# Carduino.net
KiCad netlist of a schematic drawn in EAGLE
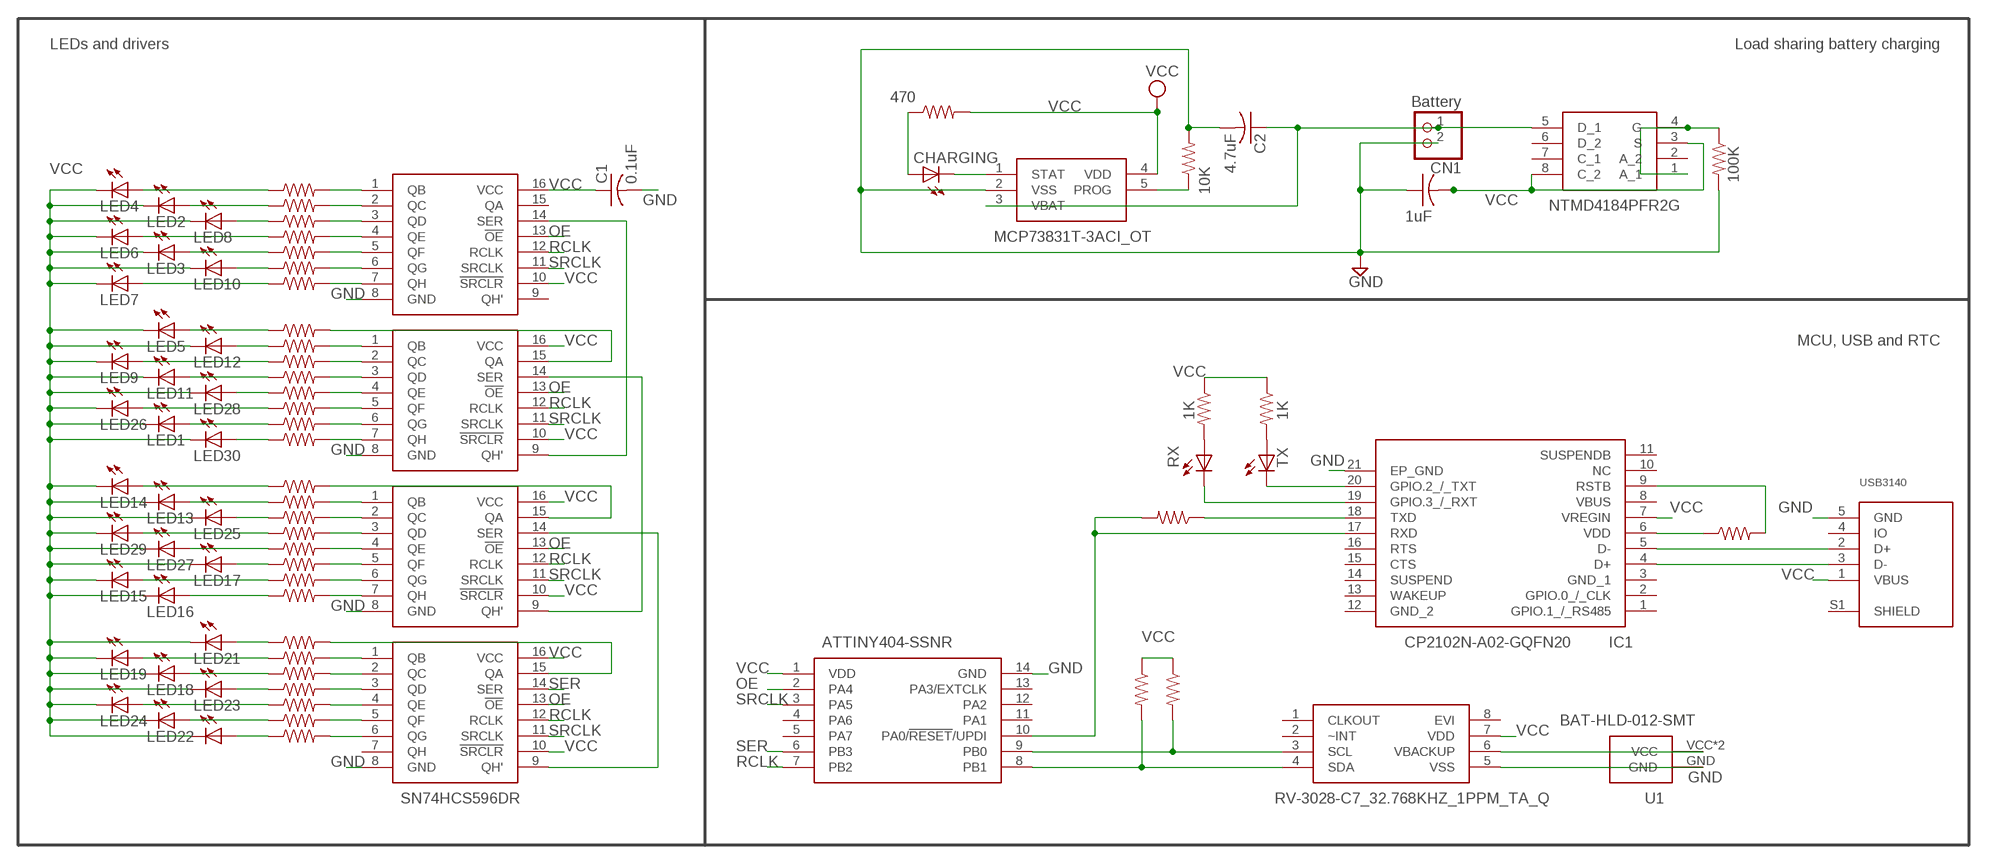
[diagram p0: schematic, sheet 1]

(export (version "E")
  (design (tool "Eeschema 10.0.6"))
  (components
    (comp (ref "C1")
      (value "0.1uF")
      (footprint "eagle-import:C1206")
      (libsource (lib "eagle-import") (part "C-USC1206"))
    )
    (comp (ref "C2")
      (value "4.7uF")
      (footprint "eagle-import:C1206")
      (libsource (lib "eagle-import") (part "C-USC1206"))
    )
    (comp (ref "C3")
      (value "1uF")
      (footprint "eagle-import:C1206")
      (libsource (lib "eagle-import") (part "C-USC1206"))
    )
    (comp (ref "CHARGING")
      (value "Red")
      (footprint "eagle-import:CHIP-LED0805")
      (libsource (lib "eagle-import") (part "LEDCHIP-LED0805"))
    )
    (comp (ref "CN1")
      (value "Battery")
      (footprint "eagle-import:JST-PH-2-SMT-RA")
      (libsource (lib "eagle-import") (part "JST_2PIN-SMT-RA"))
    )
    (comp (ref "IC1")
      (value "CP2102N-A02-GQFN20")
      (footprint "eagle-import:CP2102NA02GQFN20")
      (fields (field (name "MOUSER_PART_NUMBER") "634-CP2102NA02GQFN20"))
      (libsource (lib "eagle-import") (part "CP2102N-A02-GQFN20"))
    )
    (comp (ref "IC3")
      (value "SN74HCS596DR")
      (footprint "eagle-import:SOIC127P600X175-16N")
      (fields (field (name "MOUSER_PART_NUMBER") "595-SN74HCS596DR"))
      (libsource (lib "eagle-import") (part "SN74HCS596DR"))
    )
    (comp (ref "IC4")
      (value "SN74HCS596DR")
      (footprint "eagle-import:SOIC127P600X175-16N")
      (fields (field (name "MOUSER_PART_NUMBER") "595-SN74HCS596DR"))
      (libsource (lib "eagle-import") (part "SN74HCS596DR"))
    )
    (comp (ref "IC5")
      (value "SN74HCS596DR")
      (footprint "eagle-import:SOIC127P600X175-16N")
      (fields (field (name "MOUSER_PART_NUMBER") "595-SN74HCS596DR"))
      (libsource (lib "eagle-import") (part "SN74HCS596DR"))
    )
    (comp (ref "IC6")
      (value "SN74HCS596DR")
      (footprint "eagle-import:SOIC127P600X175-16N")
      (fields (field (name "MOUSER_PART_NUMBER") "595-SN74HCS596DR"))
      (libsource (lib "eagle-import") (part "SN74HCS596DR"))
    )
    (comp (ref "IC7")
      (value "NTMD4184PFR2G")
      (footprint "eagle-import:SOIC127P600X175-8N")
      (fields (field (name "MOUSER_PART_NUMBER") "863-NTMD4184PFR2G"))
      (libsource (lib "eagle-import") (part "NTMD4184PFR2G"))
    )
    (comp (ref "IC8")
      (value "ATTINY404-SSNR")
      (footprint "eagle-import:SOIC127P600X175-14N")
      (fields (field (name "MOUSER_PART_NUMBER") "556-ATTINY404-SSNR"))
      (libsource (lib "eagle-import") (part "ATTINY404-SSNR"))
    )
    (comp (ref "IC9")
      (value "MCP73831T-3ACI_OT")
      (footprint "eagle-import:SOT95P270X145-5N")
      (fields
        (field (name "MANUFACTURER_PART_NUMBER") "MCP73831T-3ACI/OT")
        (field (name "MOUSER_PART_NUMBER") "579-MCP73831T-3ACIOT")
      )
      (libsource (lib "eagle-import") (part "MCP73831T-3ACI_OT"))
    )
    (comp (ref "IC11")
      (value "RV-3028-C7_32.768KHZ_1PPM_TA_Q")
      (footprint "eagle-import:RV3028C732768KHZ1PPMTAQC")
      (fields
        (field (name "MANUFACTURER_PART_NUMBER") "RV-3028-C7 32.768kHz 1ppm TA QC")
        (field (name "MOUSER_PART_NUMBER") "428-203591-MG01")
      )
      (libsource (lib "eagle-import") (part "RV-3028-C7_32.768KHZ_1PPM_TA_Q"))
    )
    (comp (ref "LED1")
      (value "LUXEON2835L128-1890NA3500001")
      (footprint "eagle-import:LUXEON2835")
      (libsource (lib "eagle-import") (part "LUXEON2835L128-1890NA3500001"))
    )
    (comp (ref "LED2")
      (value "LUXEON2835L128-1890NA3500001")
      (footprint "eagle-import:LUXEON2835")
      (libsource (lib "eagle-import") (part "LUXEON2835L128-1890NA3500001"))
    )
    (comp (ref "LED3")
      (value "LUXEON2835L128-1890NA3500001")
      (footprint "eagle-import:LUXEON2835")
      (libsource (lib "eagle-import") (part "LUXEON2835L128-1890NA3500001"))
    )
    (comp (ref "LED4")
      (value "LUXEON2835L128-1890NA3500001")
      (footprint "eagle-import:LUXEON2835")
      (libsource (lib "eagle-import") (part "LUXEON2835L128-1890NA3500001"))
    )
    (comp (ref "LED5")
      (value "LUXEON2835L128-1890NA3500001")
      (footprint "eagle-import:LUXEON2835")
      (libsource (lib "eagle-import") (part "LUXEON2835L128-1890NA3500001"))
    )
    (comp (ref "LED6")
      (value "LUXEON2835L128-1890NA3500001")
      (footprint "eagle-import:LUXEON2835")
      (libsource (lib "eagle-import") (part "LUXEON2835L128-1890NA3500001"))
    )
    (comp (ref "LED7")
      (value "LUXEON2835L128-1890NA3500001")
      (footprint "eagle-import:LUXEON2835")
      (libsource (lib "eagle-import") (part "LUXEON2835L128-1890NA3500001"))
    )
    (comp (ref "LED8")
      (value "LUXEON2835L128-1890NA3500001")
      (footprint "eagle-import:LUXEON2835")
      (libsource (lib "eagle-import") (part "LUXEON2835L128-1890NA3500001"))
    )
    (comp (ref "LED9")
      (value "LUXEON2835L128-1890NA3500001")
      (footprint "eagle-import:LUXEON2835")
      (libsource (lib "eagle-import") (part "LUXEON2835L128-1890NA3500001"))
    )
    (comp (ref "LED10")
      (value "LUXEON2835L128-1890NA3500001")
      (footprint "eagle-import:LUXEON2835")
      (libsource (lib "eagle-import") (part "LUXEON2835L128-1890NA3500001"))
    )
    (comp (ref "LED11")
      (value "LUXEON2835L128-1890NA3500001")
      (footprint "eagle-import:LUXEON2835")
      (libsource (lib "eagle-import") (part "LUXEON2835L128-1890NA3500001"))
    )
    (comp (ref "LED12")
      (value "LUXEON2835L128-1890NA3500001")
      (footprint "eagle-import:LUXEON2835")
      (libsource (lib "eagle-import") (part "LUXEON2835L128-1890NA3500001"))
    )
    (comp (ref "LED13")
      (value "LUXEON2835L128-1890NA3500001")
      (footprint "eagle-import:LUXEON2835")
      (libsource (lib "eagle-import") (part "LUXEON2835L128-1890NA3500001"))
    )
    (comp (ref "LED14")
      (value "LUXEON2835L128-1890NA3500001")
      (footprint "eagle-import:LUXEON2835")
      (libsource (lib "eagle-import") (part "LUXEON2835L128-1890NA3500001"))
    )
    (comp (ref "LED15")
      (value "LUXEON2835L128-1890NA3500001")
      (footprint "eagle-import:LUXEON2835")
      (libsource (lib "eagle-import") (part "LUXEON2835L128-1890NA3500001"))
    )
    (comp (ref "LED16")
      (value "LUXEON2835L128-1890NA3500001")
      (footprint "eagle-import:LUXEON2835")
      (libsource (lib "eagle-import") (part "LUXEON2835L128-1890NA3500001"))
    )
    (comp (ref "LED17")
      (value "LUXEON2835L128-1890NA3500001")
      (footprint "eagle-import:LUXEON2835")
      (libsource (lib "eagle-import") (part "LUXEON2835L128-1890NA3500001"))
    )
    (comp (ref "LED18")
      (value "LUXEON2835L128-1890NA3500001")
      (footprint "eagle-import:LUXEON2835")
      (libsource (lib "eagle-import") (part "LUXEON2835L128-1890NA3500001"))
    )
    (comp (ref "LED19")
      (value "LUXEON2835L128-1890NA3500001")
      (footprint "eagle-import:LUXEON2835")
      (libsource (lib "eagle-import") (part "LUXEON2835L128-1890NA3500001"))
    )
    (comp (ref "LED20")
      (value "LUXEON2835L128-1890NA3500001")
      (footprint "eagle-import:LUXEON2835")
      (libsource (lib "eagle-import") (part "LUXEON2835L128-1890NA3500001"))
    )
    (comp (ref "LED21")
      (value "LUXEON2835L128-1890NA3500001")
      (footprint "eagle-import:LUXEON2835")
      (libsource (lib "eagle-import") (part "LUXEON2835L128-1890NA3500001"))
    )
    (comp (ref "LED22")
      (value "LUXEON2835L128-1890NA3500001")
      (footprint "eagle-import:LUXEON2835")
      (libsource (lib "eagle-import") (part "LUXEON2835L128-1890NA3500001"))
    )
    (comp (ref "LED23")
      (value "LUXEON2835L128-1890NA3500001")
      (footprint "eagle-import:LUXEON2835")
      (libsource (lib "eagle-import") (part "LUXEON2835L128-1890NA3500001"))
    )
    (comp (ref "LED24")
      (value "LUXEON2835L128-1890NA3500001")
      (footprint "eagle-import:LUXEON2835")
      (libsource (lib "eagle-import") (part "LUXEON2835L128-1890NA3500001"))
    )
    (comp (ref "LED25")
      (value "LUXEON2835L128-1890NA3500001")
      (footprint "eagle-import:LUXEON2835")
      (libsource (lib "eagle-import") (part "LUXEON2835L128-1890NA3500001"))
    )
    (comp (ref "LED26")
      (value "LUXEON2835L128-1890NA3500001")
      (footprint "eagle-import:LUXEON2835")
      (libsource (lib "eagle-import") (part "LUXEON2835L128-1890NA3500001"))
    )
    (comp (ref "LED27")
      (value "LUXEON2835L128-1890NA3500001")
      (footprint "eagle-import:LUXEON2835")
      (libsource (lib "eagle-import") (part "LUXEON2835L128-1890NA3500001"))
    )
    (comp (ref "LED28")
      (value "LUXEON2835L128-1890NA3500001")
      (footprint "eagle-import:LUXEON2835")
      (libsource (lib "eagle-import") (part "LUXEON2835L128-1890NA3500001"))
    )
    (comp (ref "LED29")
      (value "LUXEON2835L128-1890NA3500001")
      (footprint "eagle-import:LUXEON2835")
      (libsource (lib "eagle-import") (part "LUXEON2835L128-1890NA3500001"))
    )
    (comp (ref "LED30")
      (value "LUXEON2835L128-1890NA3500001")
      (footprint "eagle-import:LUXEON2835")
      (libsource (lib "eagle-import") (part "LUXEON2835L128-1890NA3500001"))
    )
    (comp (ref "R1")
      (value "470")
      (footprint "eagle-import:R0805")
      (libsource (lib "eagle-import") (part "R-US_R0805"))
    )
    (comp (ref "R2")
      (value "1K")
      (footprint "eagle-import:R0805")
      (libsource (lib "eagle-import") (part "R-US_R0805"))
    )
    (comp (ref "R3")
      (value "1K")
      (footprint "eagle-import:R0805")
      (libsource (lib "eagle-import") (part "R-US_R0805"))
    )
    (comp (ref "R4")
      (value "4.7K")
      (footprint "eagle-import:R0805")
      (libsource (lib "eagle-import") (part "R-US_R0805"))
    )
    (comp (ref "R5")
      (value "4.7K")
      (footprint "eagle-import:R0805")
      (libsource (lib "eagle-import") (part "R-US_R0805"))
    )
    (comp (ref "R7")
      (value "1K")
      (footprint "eagle-import:R0805")
      (libsource (lib "eagle-import") (part "R-US_R0805"))
    )
    (comp (ref "R8")
      (value "1K")
      (footprint "eagle-import:R0805")
      (libsource (lib "eagle-import") (part "R-US_R0805"))
    )
    (comp (ref "R9")
      (value "1K")
      (footprint "eagle-import:R0805")
      (libsource (lib "eagle-import") (part "R-US_R0805"))
    )
    (comp (ref "R10")
      (value "1K")
      (footprint "eagle-import:R0805")
      (libsource (lib "eagle-import") (part "R-US_R0805"))
    )
    (comp (ref "R11")
      (value "1K")
      (footprint "eagle-import:R0805")
      (libsource (lib "eagle-import") (part "R-US_R0805"))
    )
    (comp (ref "R12")
      (value "1K")
      (footprint "eagle-import:R0805")
      (libsource (lib "eagle-import") (part "R-US_R0805"))
    )
    (comp (ref "R13")
      (value "1K")
      (footprint "eagle-import:R0805")
      (libsource (lib "eagle-import") (part "R-US_R0805"))
    )
    (comp (ref "R14")
      (value "1K")
      (footprint "eagle-import:R0805")
      (libsource (lib "eagle-import") (part "R-US_R0805"))
    )
    (comp (ref "R15")
      (value "1K")
      (footprint "eagle-import:R0805")
      (libsource (lib "eagle-import") (part "R-US_R0805"))
    )
    (comp (ref "R16")
      (value "470")
      (footprint "eagle-import:R0805")
      (libsource (lib "eagle-import") (part "R-US_R0805"))
    )
    (comp (ref "R17")
      (value "1K")
      (footprint "eagle-import:R0805")
      (libsource (lib "eagle-import") (part "R-US_R0805"))
    )
    (comp (ref "R18")
      (value "1K")
      (footprint "eagle-import:R0805")
      (libsource (lib "eagle-import") (part "R-US_R0805"))
    )
    (comp (ref "R19")
      (value "1K")
      (footprint "eagle-import:R0805")
      (libsource (lib "eagle-import") (part "R-US_R0805"))
    )
    (comp (ref "R20")
      (value "1K")
      (footprint "eagle-import:R0805")
      (libsource (lib "eagle-import") (part "R-US_R0805"))
    )
    (comp (ref "R21")
      (value "100K")
      (footprint "eagle-import:R0805")
      (libsource (lib "eagle-import") (part "R-US_R0805"))
    )
    (comp (ref "R22")
      (value "10K")
      (footprint "eagle-import:R0805")
      (libsource (lib "eagle-import") (part "R-US_R0805"))
    )
    (comp (ref "R23")
      (value "1K")
      (footprint "eagle-import:R0805")
      (libsource (lib "eagle-import") (part "R-US_R0805"))
    )
    (comp (ref "R31")
      (value "1K")
      (footprint "eagle-import:R0805")
      (libsource (lib "eagle-import") (part "R-US_R0805"))
    )
    (comp (ref "R32")
      (value "1K")
      (footprint "eagle-import:R0805")
      (libsource (lib "eagle-import") (part "R-US_R0805"))
    )
    (comp (ref "R33")
      (value "1K")
      (footprint "eagle-import:R0805")
      (libsource (lib "eagle-import") (part "R-US_R0805"))
    )
    (comp (ref "R34")
      (value "1K")
      (footprint "eagle-import:R0805")
      (libsource (lib "eagle-import") (part "R-US_R0805"))
    )
    (comp (ref "R35")
      (value "1K")
      (footprint "eagle-import:R0805")
      (libsource (lib "eagle-import") (part "R-US_R0805"))
    )
    (comp (ref "R36")
      (value "1K")
      (footprint "eagle-import:R0805")
      (libsource (lib "eagle-import") (part "R-US_R0805"))
    )
    (comp (ref "R37")
      (value "1K")
      (footprint "eagle-import:R0805")
      (libsource (lib "eagle-import") (part "R-US_R0805"))
    )
    (comp (ref "R38")
      (value "1K")
      (footprint "eagle-import:R0805")
      (libsource (lib "eagle-import") (part "R-US_R0805"))
    )
    (comp (ref "R39")
      (value "1K")
      (footprint "eagle-import:R0805")
      (libsource (lib "eagle-import") (part "R-US_R0805"))
    )
    (comp (ref "R40")
      (value "1K")
      (footprint "eagle-import:R0805")
      (libsource (lib "eagle-import") (part "R-US_R0805"))
    )
    (comp (ref "R41")
      (value "1K")
      (footprint "eagle-import:R0805")
      (libsource (lib "eagle-import") (part "R-US_R0805"))
    )
    (comp (ref "R42")
      (value "1K")
      (footprint "eagle-import:R0805")
      (libsource (lib "eagle-import") (part "R-US_R0805"))
    )
    (comp (ref "R43")
      (value "1K")
      (footprint "eagle-import:R0805")
      (libsource (lib "eagle-import") (part "R-US_R0805"))
    )
    (comp (ref "R44")
      (value "1K")
      (footprint "eagle-import:R0805")
      (libsource (lib "eagle-import") (part "R-US_R0805"))
    )
    (comp (ref "R45")
      (value "1K")
      (footprint "eagle-import:R0805")
      (libsource (lib "eagle-import") (part "R-US_R0805"))
    )
    (comp (ref "R46")
      (value "1K")
      (footprint "eagle-import:R0805")
      (libsource (lib "eagle-import") (part "R-US_R0805"))
    )
    (comp (ref "R47")
      (value "1K")
      (footprint "eagle-import:R0805")
      (libsource (lib "eagle-import") (part "R-US_R0805"))
    )
    (comp (ref "RX")
      (value "Green")
      (footprint "eagle-import:CHIP-LED0805")
      (libsource (lib "eagle-import") (part "LEDCHIP-LED0805"))
    )
    (comp (ref "TX")
      (value "Red")
      (footprint "eagle-import:CHIP-LED0805")
      (libsource (lib "eagle-import") (part "LEDCHIP-LED0805"))
    )
    (comp (ref "U$5")
      (value "USB3140")
      (footprint "eagle-import:USB3140-30-0170-0-C")
      (libsource (lib "eagle-import") (part "USB3140"))
    )
    (comp (ref "U1")
      (value "BAT-HLD-012-SMT")
      (footprint "eagle-import:BATHLD012SMT")
      (fields (field (name "MOUSER_PART_NUMBER") "712-BAT-HLD-012-SMT"))
      (libsource (lib "eagle-import") (part "BAT-HLD-012-SMT"))
    )
  )
  (nets
    (net (code "1") (name "/OE") (class "Default")
      (node (ref "IC3") (pin "13") (pinfunction "~{OE}_13") (pintype "bidirectional"))
      (node (ref "IC4") (pin "13") (pinfunction "~{OE}_13") (pintype "bidirectional"))
      (node (ref "IC5") (pin "13") (pinfunction "~{OE}_13") (pintype "bidirectional"))
      (node (ref "IC6") (pin "13") (pinfunction "~{OE}_13") (pintype "bidirectional"))
      (node (ref "IC8") (pin "2") (pinfunction "PA4_2") (pintype "bidirectional"))
    )
    (net (code "2") (name "/RCLK") (class "Default")
      (node (ref "IC3") (pin "12") (pinfunction "RCLK_12") (pintype "bidirectional"))
      (node (ref "IC4") (pin "12") (pinfunction "RCLK_12") (pintype "bidirectional"))
      (node (ref "IC5") (pin "12") (pinfunction "RCLK_12") (pintype "bidirectional"))
      (node (ref "IC6") (pin "12") (pinfunction "RCLK_12") (pintype "bidirectional"))
      (node (ref "IC8") (pin "7") (pinfunction "PB2_7") (pintype "bidirectional"))
    )
    (net (code "3") (name "/SER") (class "Default")
      (node (ref "IC6") (pin "14") (pinfunction "SER_14") (pintype "bidirectional"))
      (node (ref "IC8") (pin "6") (pinfunction "PB3_6") (pintype "bidirectional"))
    )
    (net (code "4") (name "/SRCLK") (class "Default")
      (node (ref "IC3") (pin "11") (pinfunction "SRCLK_11") (pintype "bidirectional"))
      (node (ref "IC4") (pin "11") (pinfunction "SRCLK_11") (pintype "bidirectional"))
      (node (ref "IC5") (pin "11") (pinfunction "SRCLK_11") (pintype "bidirectional"))
      (node (ref "IC6") (pin "11") (pinfunction "SRCLK_11") (pintype "bidirectional"))
      (node (ref "IC8") (pin "3") (pinfunction "PA5_3") (pintype "bidirectional"))
    )
    (net (code "5") (name "GND") (class "Default")
      (node (ref "C1") (pin "2") (pinfunction "2_2") (pintype "passive"))
      (node (ref "C2") (pin "2") (pinfunction "2_2") (pintype "passive"))
      (node (ref "C3") (pin "1") (pinfunction "1_1") (pintype "passive"))
      (node (ref "CN1") (pin "2") (pinfunction "1_2") (pintype "passive"))
      (node (ref "IC1") (pin "21") (pinfunction "EP_GND_21") (pintype "bidirectional"))
      (node (ref "IC11") (pin "5") (pinfunction "VSS_5") (pintype "bidirectional"))
      (node (ref "IC3") (pin "8") (pinfunction "GND_8") (pintype "bidirectional"))
      (node (ref "IC4") (pin "8") (pinfunction "GND_8") (pintype "bidirectional"))
      (node (ref "IC5") (pin "8") (pinfunction "GND_8") (pintype "bidirectional"))
      (node (ref "IC6") (pin "8") (pinfunction "GND_8") (pintype "bidirectional"))
      (node (ref "IC8") (pin "14") (pinfunction "GND_14") (pintype "bidirectional"))
      (node (ref "IC9") (pin "2") (pinfunction "VSS_2") (pintype "bidirectional"))
      (node (ref "R21") (pin "2") (pinfunction "2_2") (pintype "passive"))
      (node (ref "R22") (pin "2") (pinfunction "2_2") (pintype "passive"))
      (node (ref "U$5") (pin "5") (pinfunction "GND_5") (pintype "passive"))
      (node (ref "U1") (pin "GND") (pinfunction "GND_GND") (pintype "bidirectional"))
    )
    (net (code "6") (name "Net-(CHARGING-PadA)") (class "Default")
      (node (ref "CHARGING") (pin "A") (pinfunction "A_A") (pintype "passive"))
      (node (ref "R16") (pin "1") (pinfunction "1_1") (pintype "passive"))
    )
    (net (code "7") (name "Net-(CN1-2)") (class "Default")
      (node (ref "C2") (pin "1") (pinfunction "1_1") (pintype "passive"))
      (node (ref "CN1") (pin "1") (pinfunction "2_1") (pintype "passive"))
      (node (ref "IC7") (pin "5") (pinfunction "D_1_5") (pintype "bidirectional"))
      (node (ref "IC9") (pin "3") (pinfunction "VBAT_3") (pintype "bidirectional"))
    )
    (net (code "8") (name "Net-(IC1-D+)") (class "Default")
      (node (ref "IC1") (pin "4") (pinfunction "D+_4") (pintype "bidirectional"))
      (node (ref "U$5") (pin "3") (pinfunction "D-_3") (pintype "passive"))
    )
    (net (code "9") (name "Net-(IC1-D-)") (class "Default")
      (node (ref "IC1") (pin "5") (pinfunction "D-_5") (pintype "bidirectional"))
      (node (ref "U$5") (pin "2") (pinfunction "D+_2") (pintype "passive"))
    )
    (net (code "10") (name "Net-(IC1-GPIO.2_{slash}_TXT)") (class "Default")
      (node (ref "IC1") (pin "20") (pinfunction "GPIO.2_/_TXT_20") (pintype "bidirectional"))
      (node (ref "TX") (pin "C") (pinfunction "C_C") (pintype "passive"))
    )
    (net (code "11") (name "Net-(IC1-GPIO.3_{slash}_RXT)") (class "Default")
      (node (ref "IC1") (pin "19") (pinfunction "GPIO.3_/_RXT_19") (pintype "bidirectional"))
      (node (ref "RX") (pin "C") (pinfunction "C_C") (pintype "passive"))
    )
    (net (code "12") (name "Net-(IC1-RSTB)") (class "Default")
      (node (ref "IC1") (pin "9") (pinfunction "RSTB_9") (pintype "bidirectional"))
      (node (ref "R23") (pin "2") (pinfunction "2_2") (pintype "passive"))
    )
    (net (code "13") (name "Net-(IC1-RXD)") (class "Default")
      (node (ref "IC1") (pin "17") (pinfunction "RXD_17") (pintype "bidirectional"))
      (node (ref "IC8") (pin "10") (pinfunction "PA0/~{RESET}/UPDI_10") (pintype "bidirectional"))
      (node (ref "R1") (pin "2") (pinfunction "2_2") (pintype "passive"))
    )
    (net (code "14") (name "Net-(IC1-TXD)") (class "Default")
      (node (ref "IC1") (pin "18") (pinfunction "TXD_18") (pintype "bidirectional"))
      (node (ref "R1") (pin "1") (pinfunction "1_1") (pintype "passive"))
    )
    (net (code "15") (name "Net-(IC1-VDD)") (class "Default")
      (node (ref "IC1") (pin "6") (pinfunction "VDD_6") (pintype "bidirectional"))
      (node (ref "R23") (pin "1") (pinfunction "1_1") (pintype "passive"))
    )
    (net (code "16") (name "Net-(IC3-QB)") (class "Default")
      (node (ref "IC3") (pin "1") (pinfunction "QB_1") (pintype "bidirectional"))
      (node (ref "R15") (pin "2") (pinfunction "2_2") (pintype "passive"))
    )
    (net (code "17") (name "Net-(IC3-QC)") (class "Default")
      (node (ref "IC3") (pin "2") (pinfunction "QC_2") (pintype "bidirectional"))
      (node (ref "R14") (pin "2") (pinfunction "2_2") (pintype "passive"))
    )
    (net (code "18") (name "Net-(IC3-QD)") (class "Default")
      (node (ref "IC3") (pin "3") (pinfunction "QD_3") (pintype "bidirectional"))
      (node (ref "R13") (pin "2") (pinfunction "2_2") (pintype "passive"))
    )
    (net (code "19") (name "Net-(IC3-QE)") (class "Default")
      (node (ref "IC3") (pin "4") (pinfunction "QE_4") (pintype "bidirectional"))
      (node (ref "R12") (pin "2") (pinfunction "2_2") (pintype "passive"))
    )
    (net (code "20") (name "Net-(IC3-QF)") (class "Default")
      (node (ref "IC3") (pin "5") (pinfunction "QF_5") (pintype "bidirectional"))
      (node (ref "R11") (pin "2") (pinfunction "2_2") (pintype "passive"))
    )
    (net (code "21") (name "Net-(IC3-QG)") (class "Default")
      (node (ref "IC3") (pin "6") (pinfunction "QG_6") (pintype "bidirectional"))
      (node (ref "R10") (pin "2") (pinfunction "2_2") (pintype "passive"))
    )
    (net (code "22") (name "Net-(IC3-QH)") (class "Default")
      (node (ref "IC3") (pin "7") (pinfunction "QH_7") (pintype "bidirectional"))
      (node (ref "R9") (pin "2") (pinfunction "2_2") (pintype "passive"))
    )
    (net (code "23") (name "Net-(IC3-SER)") (class "Default")
      (node (ref "IC3") (pin "14") (pinfunction "SER_14") (pintype "bidirectional"))
      (node (ref "IC4") (pin "9") (pinfunction "QH'_9") (pintype "bidirectional"))
    )
    (net (code "24") (name "Net-(IC4-QA)") (class "Default")
      (node (ref "IC4") (pin "15") (pinfunction "QA_15") (pintype "bidirectional"))
      (node (ref "R8") (pin "2") (pinfunction "2_2") (pintype "passive"))
    )
    (net (code "25") (name "Net-(IC4-QB)") (class "Default")
      (node (ref "IC4") (pin "1") (pinfunction "QB_1") (pintype "bidirectional"))
      (node (ref "R7") (pin "2") (pinfunction "2_2") (pintype "passive"))
    )
    (net (code "26") (name "Net-(IC4-QC)") (class "Default")
      (node (ref "IC4") (pin "2") (pinfunction "QC_2") (pintype "bidirectional"))
      (node (ref "R17") (pin "2") (pinfunction "2_2") (pintype "passive"))
    )
    (net (code "27") (name "Net-(IC4-QD)") (class "Default")
      (node (ref "IC4") (pin "3") (pinfunction "QD_3") (pintype "bidirectional"))
      (node (ref "R18") (pin "2") (pinfunction "2_2") (pintype "passive"))
    )
    (net (code "28") (name "Net-(IC4-QE)") (class "Default")
      (node (ref "IC4") (pin "4") (pinfunction "QE_4") (pintype "bidirectional"))
      (node (ref "R19") (pin "2") (pinfunction "2_2") (pintype "passive"))
    )
    (net (code "29") (name "Net-(IC4-QF)") (class "Default")
      (node (ref "IC4") (pin "5") (pinfunction "QF_5") (pintype "bidirectional"))
      (node (ref "R20") (pin "2") (pinfunction "2_2") (pintype "passive"))
    )
    (net (code "30") (name "Net-(IC4-QG)") (class "Default")
      (node (ref "IC4") (pin "6") (pinfunction "QG_6") (pintype "bidirectional"))
      (node (ref "R31") (pin "2") (pinfunction "2_2") (pintype "passive"))
    )
    (net (code "31") (name "Net-(IC4-QH)") (class "Default")
      (node (ref "IC4") (pin "7") (pinfunction "QH_7") (pintype "bidirectional"))
      (node (ref "R32") (pin "2") (pinfunction "2_2") (pintype "passive"))
    )
    (net (code "32") (name "Net-(IC4-SER)") (class "Default")
      (node (ref "IC4") (pin "14") (pinfunction "SER_14") (pintype "bidirectional"))
      (node (ref "IC5") (pin "9") (pinfunction "QH'_9") (pintype "bidirectional"))
    )
    (net (code "33") (name "Net-(IC5-QA)") (class "Default")
      (node (ref "IC5") (pin "15") (pinfunction "QA_15") (pintype "bidirectional"))
      (node (ref "R33") (pin "2") (pinfunction "2_2") (pintype "passive"))
    )
    (net (code "34") (name "Net-(IC5-QB)") (class "Default")
      (node (ref "IC5") (pin "1") (pinfunction "QB_1") (pintype "bidirectional"))
      (node (ref "R34") (pin "2") (pinfunction "2_2") (pintype "passive"))
    )
    (net (code "35") (name "Net-(IC5-QC)") (class "Default")
      (node (ref "IC5") (pin "2") (pinfunction "QC_2") (pintype "bidirectional"))
      (node (ref "R35") (pin "2") (pinfunction "2_2") (pintype "passive"))
    )
    (net (code "36") (name "Net-(IC5-QD)") (class "Default")
      (node (ref "IC5") (pin "3") (pinfunction "QD_3") (pintype "bidirectional"))
      (node (ref "R36") (pin "2") (pinfunction "2_2") (pintype "passive"))
    )
    (net (code "37") (name "Net-(IC5-QE)") (class "Default")
      (node (ref "IC5") (pin "4") (pinfunction "QE_4") (pintype "bidirectional"))
      (node (ref "R37") (pin "2") (pinfunction "2_2") (pintype "passive"))
    )
    (net (code "38") (name "Net-(IC5-QF)") (class "Default")
      (node (ref "IC5") (pin "5") (pinfunction "QF_5") (pintype "bidirectional"))
      (node (ref "R38") (pin "2") (pinfunction "2_2") (pintype "passive"))
    )
    (net (code "39") (name "Net-(IC5-QG)") (class "Default")
      (node (ref "IC5") (pin "6") (pinfunction "QG_6") (pintype "bidirectional"))
      (node (ref "R39") (pin "2") (pinfunction "2_2") (pintype "passive"))
    )
    (net (code "40") (name "Net-(IC5-QH)") (class "Default")
      (node (ref "IC5") (pin "7") (pinfunction "QH_7") (pintype "bidirectional"))
      (node (ref "R40") (pin "2") (pinfunction "2_2") (pintype "passive"))
    )
    (net (code "41") (name "Net-(IC5-SER)") (class "Default")
      (node (ref "IC5") (pin "14") (pinfunction "SER_14") (pintype "bidirectional"))
      (node (ref "IC6") (pin "9") (pinfunction "QH'_9") (pintype "bidirectional"))
    )
    (net (code "42") (name "Net-(IC6-QA)") (class "Default")
      (node (ref "IC6") (pin "15") (pinfunction "QA_15") (pintype "bidirectional"))
      (node (ref "R41") (pin "2") (pinfunction "2_2") (pintype "passive"))
    )
    (net (code "43") (name "Net-(IC6-QB)") (class "Default")
      (node (ref "IC6") (pin "1") (pinfunction "QB_1") (pintype "bidirectional"))
      (node (ref "R42") (pin "2") (pinfunction "2_2") (pintype "passive"))
    )
    (net (code "44") (name "Net-(IC6-QC)") (class "Default")
      (node (ref "IC6") (pin "2") (pinfunction "QC_2") (pintype "bidirectional"))
      (node (ref "R43") (pin "2") (pinfunction "2_2") (pintype "passive"))
    )
    (net (code "45") (name "Net-(IC6-QD)") (class "Default")
      (node (ref "IC6") (pin "3") (pinfunction "QD_3") (pintype "bidirectional"))
      (node (ref "R44") (pin "2") (pinfunction "2_2") (pintype "passive"))
    )
    (net (code "46") (name "Net-(IC6-QE)") (class "Default")
      (node (ref "IC6") (pin "4") (pinfunction "QE_4") (pintype "bidirectional"))
      (node (ref "R45") (pin "2") (pinfunction "2_2") (pintype "passive"))
    )
    (net (code "47") (name "Net-(IC6-QF)") (class "Default")
      (node (ref "IC6") (pin "5") (pinfunction "QF_5") (pintype "bidirectional"))
      (node (ref "R46") (pin "2") (pinfunction "2_2") (pintype "passive"))
    )
    (net (code "48") (name "Net-(IC6-QG)") (class "Default")
      (node (ref "IC6") (pin "6") (pinfunction "QG_6") (pintype "bidirectional"))
      (node (ref "R47") (pin "2") (pinfunction "2_2") (pintype "passive"))
    )
    (net (code "49") (name "Net-(IC7-A_1)") (class "Default")
      (node (ref "IC7") (pin "1") (pinfunction "A_1_1") (pintype "bidirectional"))
      (node (ref "IC7") (pin "4") (pinfunction "G_4") (pintype "bidirectional"))
      (node (ref "R21") (pin "1") (pinfunction "1_1") (pintype "passive"))
    )
    (net (code "50") (name "Net-(IC9-PROG)") (class "Default")
      (node (ref "IC9") (pin "5") (pinfunction "PROG_5") (pintype "bidirectional"))
      (node (ref "R22") (pin "1") (pinfunction "1_1") (pintype "passive"))
    )
    (net (code "51") (name "Net-(IC9-STAT)") (class "Default")
      (node (ref "CHARGING") (pin "C") (pinfunction "C_C") (pintype "passive"))
      (node (ref "IC9") (pin "1") (pinfunction "STAT_1") (pintype "bidirectional"))
    )
    (net (code "52") (name "Net-(IC11-SCL)") (class "Default")
      (node (ref "IC11") (pin "3") (pinfunction "SCL_3") (pintype "bidirectional"))
      (node (ref "IC8") (pin "9") (pinfunction "PB0_9") (pintype "bidirectional"))
      (node (ref "R5") (pin "2") (pinfunction "2_2") (pintype "passive"))
    )
    (net (code "53") (name "Net-(IC11-SDA)") (class "Default")
      (node (ref "IC11") (pin "4") (pinfunction "SDA_4") (pintype "bidirectional"))
      (node (ref "IC8") (pin "8") (pinfunction "PB1_8") (pintype "bidirectional"))
      (node (ref "R4") (pin "2") (pinfunction "2_2") (pintype "passive"))
    )
    (net (code "54") (name "Net-(IC11-VBACKUP)") (class "Default")
      (node (ref "IC11") (pin "6") (pinfunction "VBACKUP_6") (pintype "bidirectional"))
      (node (ref "U1") (pin "VCC") (pinfunction "VCC_VCC") (pintype "bidirectional"))
      (node (ref "U1") (pin "VCC2") (pinfunction "VCC_VCC2") (pintype "bidirectional"))
    )
    (net (code "55") (name "Net-(LED1-A)") (class "Default")
      (node (ref "LED1") (pin "ANODE") (pinfunction "A_ANODE") (pintype "passive"))
      (node (ref "R31") (pin "1") (pinfunction "1_1") (pintype "passive"))
    )
    (net (code "56") (name "Net-(LED2-A)") (class "Default")
      (node (ref "LED2") (pin "ANODE") (pinfunction "A_ANODE") (pintype "passive"))
      (node (ref "R14") (pin "1") (pinfunction "1_1") (pintype "passive"))
    )
    (net (code "57") (name "Net-(LED3-A)") (class "Default")
      (node (ref "LED3") (pin "ANODE") (pinfunction "A_ANODE") (pintype "passive"))
      (node (ref "R11") (pin "1") (pinfunction "1_1") (pintype "passive"))
    )
    (net (code "58") (name "Net-(LED4-A)") (class "Default")
      (node (ref "LED4") (pin "ANODE") (pinfunction "A_ANODE") (pintype "passive"))
      (node (ref "R15") (pin "1") (pinfunction "1_1") (pintype "passive"))
    )
    (net (code "59") (name "Net-(LED5-A)") (class "Default")
      (node (ref "LED5") (pin "ANODE") (pinfunction "A_ANODE") (pintype "passive"))
      (node (ref "R8") (pin "1") (pinfunction "1_1") (pintype "passive"))
    )
    (net (code "60") (name "Net-(LED6-A)") (class "Default")
      (node (ref "LED6") (pin "ANODE") (pinfunction "A_ANODE") (pintype "passive"))
      (node (ref "R12") (pin "1") (pinfunction "1_1") (pintype "passive"))
    )
    (net (code "61") (name "Net-(LED7-A)") (class "Default")
      (node (ref "LED7") (pin "ANODE") (pinfunction "A_ANODE") (pintype "passive"))
      (node (ref "R9") (pin "1") (pinfunction "1_1") (pintype "passive"))
    )
    (net (code "62") (name "Net-(LED8-A)") (class "Default")
      (node (ref "LED8") (pin "ANODE") (pinfunction "A_ANODE") (pintype "passive"))
      (node (ref "R13") (pin "1") (pinfunction "1_1") (pintype "passive"))
    )
    (net (code "63") (name "Net-(LED9-A)") (class "Default")
      (node (ref "LED9") (pin "ANODE") (pinfunction "A_ANODE") (pintype "passive"))
      (node (ref "R17") (pin "1") (pinfunction "1_1") (pintype "passive"))
    )
    (net (code "64") (name "Net-(LED10-A)") (class "Default")
      (node (ref "LED10") (pin "ANODE") (pinfunction "A_ANODE") (pintype "passive"))
      (node (ref "R10") (pin "1") (pinfunction "1_1") (pintype "passive"))
    )
    (net (code "65") (name "Net-(LED11-A)") (class "Default")
      (node (ref "LED11") (pin "ANODE") (pinfunction "A_ANODE") (pintype "passive"))
      (node (ref "R18") (pin "1") (pinfunction "1_1") (pintype "passive"))
    )
    (net (code "66") (name "Net-(LED12-A)") (class "Default")
      (node (ref "LED12") (pin "ANODE") (pinfunction "A_ANODE") (pintype "passive"))
      (node (ref "R7") (pin "1") (pinfunction "1_1") (pintype "passive"))
    )
    (net (code "67") (name "Net-(LED13-A)") (class "Default")
      (node (ref "LED13") (pin "ANODE") (pinfunction "A_ANODE") (pintype "passive"))
      (node (ref "R34") (pin "1") (pinfunction "1_1") (pintype "passive"))
    )
    (net (code "68") (name "Net-(LED14-A)") (class "Default")
      (node (ref "LED14") (pin "ANODE") (pinfunction "A_ANODE") (pintype "passive"))
      (node (ref "R33") (pin "1") (pinfunction "1_1") (pintype "passive"))
    )
    (net (code "69") (name "Net-(LED15-A)") (class "Default")
      (node (ref "LED15") (pin "ANODE") (pinfunction "A_ANODE") (pintype "passive"))
      (node (ref "R39") (pin "1") (pinfunction "1_1") (pintype "passive"))
    )
    (net (code "70") (name "Net-(LED16-A)") (class "Default")
      (node (ref "LED16") (pin "ANODE") (pinfunction "A_ANODE") (pintype "passive"))
      (node (ref "R40") (pin "1") (pinfunction "1_1") (pintype "passive"))
    )
    (net (code "71") (name "Net-(LED17-A)") (class "Default")
      (node (ref "LED17") (pin "ANODE") (pinfunction "A_ANODE") (pintype "passive"))
      (node (ref "R38") (pin "1") (pinfunction "1_1") (pintype "passive"))
    )
    (net (code "72") (name "Net-(LED18-A)") (class "Default")
      (node (ref "LED18") (pin "ANODE") (pinfunction "A_ANODE") (pintype "passive"))
      (node (ref "R43") (pin "1") (pinfunction "1_1") (pintype "passive"))
    )
    (net (code "73") (name "Net-(LED19-A)") (class "Default")
      (node (ref "LED19") (pin "ANODE") (pinfunction "A_ANODE") (pintype "passive"))
      (node (ref "R42") (pin "1") (pinfunction "1_1") (pintype "passive"))
    )
    (net (code "74") (name "Net-(LED20-A)") (class "Default")
      (node (ref "LED20") (pin "ANODE") (pinfunction "A_ANODE") (pintype "passive"))
      (node (ref "R47") (pin "1") (pinfunction "1_1") (pintype "passive"))
    )
    (net (code "75") (name "Net-(LED21-A)") (class "Default")
      (node (ref "LED21") (pin "ANODE") (pinfunction "A_ANODE") (pintype "passive"))
      (node (ref "R41") (pin "1") (pinfunction "1_1") (pintype "passive"))
    )
    (net (code "76") (name "Net-(LED22-A)") (class "Default")
      (node (ref "LED22") (pin "ANODE") (pinfunction "A_ANODE") (pintype "passive"))
      (node (ref "R46") (pin "1") (pinfunction "1_1") (pintype "passive"))
    )
    (net (code "77") (name "Net-(LED23-A)") (class "Default")
      (node (ref "LED23") (pin "ANODE") (pinfunction "A_ANODE") (pintype "passive"))
      (node (ref "R44") (pin "1") (pinfunction "1_1") (pintype "passive"))
    )
    (net (code "78") (name "Net-(LED24-A)") (class "Default")
      (node (ref "LED24") (pin "ANODE") (pinfunction "A_ANODE") (pintype "passive"))
      (node (ref "R45") (pin "1") (pinfunction "1_1") (pintype "passive"))
    )
    (net (code "79") (name "Net-(LED25-A)") (class "Default")
      (node (ref "LED25") (pin "ANODE") (pinfunction "A_ANODE") (pintype "passive"))
      (node (ref "R35") (pin "1") (pinfunction "1_1") (pintype "passive"))
    )
    (net (code "80") (name "Net-(LED26-A)") (class "Default")
      (node (ref "LED26") (pin "ANODE") (pinfunction "A_ANODE") (pintype "passive"))
      (node (ref "R20") (pin "1") (pinfunction "1_1") (pintype "passive"))
    )
    (net (code "81") (name "Net-(LED27-A)") (class "Default")
      (node (ref "LED27") (pin "ANODE") (pinfunction "A_ANODE") (pintype "passive"))
      (node (ref "R37") (pin "1") (pinfunction "1_1") (pintype "passive"))
    )
    (net (code "82") (name "Net-(LED28-A)") (class "Default")
      (node (ref "LED28") (pin "ANODE") (pinfunction "A_ANODE") (pintype "passive"))
      (node (ref "R19") (pin "1") (pinfunction "1_1") (pintype "passive"))
    )
    (net (code "83") (name "Net-(LED29-A)") (class "Default")
      (node (ref "LED29") (pin "ANODE") (pinfunction "A_ANODE") (pintype "passive"))
      (node (ref "R36") (pin "1") (pinfunction "1_1") (pintype "passive"))
    )
    (net (code "84") (name "Net-(LED30-A)") (class "Default")
      (node (ref "LED30") (pin "ANODE") (pinfunction "A_ANODE") (pintype "passive"))
      (node (ref "R32") (pin "1") (pinfunction "1_1") (pintype "passive"))
    )
    (net (code "85") (name "Net-(R2-Pad2)") (class "Default")
      (node (ref "R2") (pin "2") (pinfunction "2_2") (pintype "passive"))
      (node (ref "RX") (pin "A") (pinfunction "A_A") (pintype "passive"))
    )
    (net (code "86") (name "Net-(R3-Pad2)") (class "Default")
      (node (ref "R3") (pin "2") (pinfunction "2_2") (pintype "passive"))
      (node (ref "TX") (pin "A") (pinfunction "A_A") (pintype "passive"))
    )
    (net (code "87") (name "VCC") (class "Default")
      (node (ref "C1") (pin "1") (pinfunction "1_1") (pintype "passive"))
      (node (ref "C3") (pin "2") (pinfunction "2_2") (pintype "passive"))
      (node (ref "IC1") (pin "7") (pinfunction "VREGIN_7") (pintype "bidirectional"))
      (node (ref "IC11") (pin "7") (pinfunction "VDD_7") (pintype "bidirectional"))
      (node (ref "IC3") (pin "10") (pinfunction "~{SRCLR}_10") (pintype "bidirectional"))
      (node (ref "IC3") (pin "16") (pinfunction "VCC_16") (pintype "bidirectional"))
      (node (ref "IC4") (pin "10") (pinfunction "~{SRCLR}_10") (pintype "bidirectional"))
      (node (ref "IC4") (pin "16") (pinfunction "VCC_16") (pintype "bidirectional"))
      (node (ref "IC5") (pin "10") (pinfunction "~{SRCLR}_10") (pintype "bidirectional"))
      (node (ref "IC5") (pin "16") (pinfunction "VCC_16") (pintype "bidirectional"))
      (node (ref "IC6") (pin "10") (pinfunction "~{SRCLR}_10") (pintype "bidirectional"))
      (node (ref "IC6") (pin "16") (pinfunction "VCC_16") (pintype "bidirectional"))
      (node (ref "IC7") (pin "3") (pinfunction "S_3") (pintype "bidirectional"))
      (node (ref "IC7") (pin "8") (pinfunction "C_2_8") (pintype "bidirectional"))
      (node (ref "IC8") (pin "1") (pinfunction "VDD_1") (pintype "bidirectional"))
      (node (ref "IC9") (pin "4") (pinfunction "VDD_4") (pintype "bidirectional"))
      (node (ref "LED1") (pin "CATHODE") (pinfunction "C_CATHODE") (pintype "passive"))
      (node (ref "LED10") (pin "CATHODE") (pinfunction "C_CATHODE") (pintype "passive"))
      (node (ref "LED11") (pin "CATHODE") (pinfunction "C_CATHODE") (pintype "passive"))
      (node (ref "LED12") (pin "CATHODE") (pinfunction "C_CATHODE") (pintype "passive"))
      (node (ref "LED13") (pin "CATHODE") (pinfunction "C_CATHODE") (pintype "passive"))
      (node (ref "LED14") (pin "CATHODE") (pinfunction "C_CATHODE") (pintype "passive"))
      (node (ref "LED15") (pin "CATHODE") (pinfunction "C_CATHODE") (pintype "passive"))
      (node (ref "LED16") (pin "CATHODE") (pinfunction "C_CATHODE") (pintype "passive"))
      (node (ref "LED17") (pin "CATHODE") (pinfunction "C_CATHODE") (pintype "passive"))
      (node (ref "LED18") (pin "CATHODE") (pinfunction "C_CATHODE") (pintype "passive"))
      (node (ref "LED19") (pin "CATHODE") (pinfunction "C_CATHODE") (pintype "passive"))
      (node (ref "LED2") (pin "CATHODE") (pinfunction "C_CATHODE") (pintype "passive"))
      (node (ref "LED20") (pin "CATHODE") (pinfunction "C_CATHODE") (pintype "passive"))
      (node (ref "LED21") (pin "CATHODE") (pinfunction "C_CATHODE") (pintype "passive"))
      (node (ref "LED22") (pin "CATHODE") (pinfunction "C_CATHODE") (pintype "passive"))
      (node (ref "LED23") (pin "CATHODE") (pinfunction "C_CATHODE") (pintype "passive"))
      (node (ref "LED24") (pin "CATHODE") (pinfunction "C_CATHODE") (pintype "passive"))
      (node (ref "LED25") (pin "CATHODE") (pinfunction "C_CATHODE") (pintype "passive"))
      (node (ref "LED26") (pin "CATHODE") (pinfunction "C_CATHODE") (pintype "passive"))
      (node (ref "LED27") (pin "CATHODE") (pinfunction "C_CATHODE") (pintype "passive"))
      (node (ref "LED28") (pin "CATHODE") (pinfunction "C_CATHODE") (pintype "passive"))
      (node (ref "LED29") (pin "CATHODE") (pinfunction "C_CATHODE") (pintype "passive"))
      (node (ref "LED3") (pin "CATHODE") (pinfunction "C_CATHODE") (pintype "passive"))
      (node (ref "LED30") (pin "CATHODE") (pinfunction "C_CATHODE") (pintype "passive"))
      (node (ref "LED4") (pin "CATHODE") (pinfunction "C_CATHODE") (pintype "passive"))
      (node (ref "LED5") (pin "CATHODE") (pinfunction "C_CATHODE") (pintype "passive"))
      (node (ref "LED6") (pin "CATHODE") (pinfunction "C_CATHODE") (pintype "passive"))
      (node (ref "LED7") (pin "CATHODE") (pinfunction "C_CATHODE") (pintype "passive"))
      (node (ref "LED8") (pin "CATHODE") (pinfunction "C_CATHODE") (pintype "passive"))
      (node (ref "LED9") (pin "CATHODE") (pinfunction "C_CATHODE") (pintype "passive"))
      (node (ref "R16") (pin "2") (pinfunction "2_2") (pintype "passive"))
      (node (ref "R2") (pin "1") (pinfunction "1_1") (pintype "passive"))
      (node (ref "R3") (pin "1") (pinfunction "1_1") (pintype "passive"))
      (node (ref "R4") (pin "1") (pinfunction "1_1") (pintype "passive"))
      (node (ref "R5") (pin "1") (pinfunction "1_1") (pintype "passive"))
      (node (ref "U$5") (pin "1") (pinfunction "VBUS_1") (pintype "passive"))
    )
    (net (code "88") (name "unconnected-(IC1-CTS-Pad15)") (class "Default")
      (node (ref "IC1") (pin "15") (pinfunction "CTS_15") (pintype "bidirectional"))
    )
    (net (code "89") (name "unconnected-(IC1-GND_1-Pad3)") (class "Default")
      (node (ref "IC1") (pin "3") (pinfunction "GND_1_3") (pintype "bidirectional"))
    )
    (net (code "90") (name "unconnected-(IC1-GND_2-Pad12)") (class "Default")
      (node (ref "IC1") (pin "12") (pinfunction "GND_2_12") (pintype "bidirectional"))
    )
    (net (code "91") (name "unconnected-(IC1-GPIO.0_{slash}_CLK-Pad2)") (class "Default")
      (node (ref "IC1") (pin "2") (pinfunction "GPIO.0_/_CLK_2") (pintype "bidirectional"))
    )
    (net (code "92") (name "unconnected-(IC1-GPIO.1_{slash}_RS485-Pad1)") (class "Default")
      (node (ref "IC1") (pin "1") (pinfunction "GPIO.1_/_RS485_1") (pintype "bidirectional"))
    )
    (net (code "93") (name "unconnected-(IC1-NC-Pad10)") (class "Default")
      (node (ref "IC1") (pin "10") (pinfunction "NC_10") (pintype "no_connect"))
    )
    (net (code "94") (name "unconnected-(IC1-RTS-Pad16)") (class "Default")
      (node (ref "IC1") (pin "16") (pinfunction "RTS_16") (pintype "bidirectional"))
    )
    (net (code "95") (name "unconnected-(IC1-SUSPEND-Pad14)") (class "Default")
      (node (ref "IC1") (pin "14") (pinfunction "SUSPEND_14") (pintype "bidirectional"))
    )
    (net (code "96") (name "unconnected-(IC1-SUSPENDB-Pad11)") (class "Default")
      (node (ref "IC1") (pin "11") (pinfunction "SUSPENDB_11") (pintype "bidirectional"))
    )
    (net (code "97") (name "unconnected-(IC1-VBUS-Pad8)") (class "Default")
      (node (ref "IC1") (pin "8") (pinfunction "VBUS_8") (pintype "bidirectional"))
    )
    (net (code "98") (name "unconnected-(IC1-WAKEUP-Pad13)") (class "Default")
      (node (ref "IC1") (pin "13") (pinfunction "WAKEUP_13") (pintype "bidirectional"))
    )
    (net (code "99") (name "unconnected-(IC3-QA-Pad15)") (class "Default")
      (node (ref "IC3") (pin "15") (pinfunction "QA_15") (pintype "bidirectional"))
    )
    (net (code "100") (name "unconnected-(IC3-QH'-Pad9)") (class "Default")
      (node (ref "IC3") (pin "9") (pinfunction "QH'_9") (pintype "bidirectional"))
    )
    (net (code "101") (name "unconnected-(IC6-QH-Pad7)") (class "Default")
      (node (ref "IC6") (pin "7") (pinfunction "QH_7") (pintype "bidirectional"))
    )
    (net (code "102") (name "unconnected-(IC7-A_2-Pad2)") (class "Default")
      (node (ref "IC7") (pin "2") (pinfunction "A_2_2") (pintype "bidirectional"))
    )
    (net (code "103") (name "unconnected-(IC7-C_1-Pad7)") (class "Default")
      (node (ref "IC7") (pin "7") (pinfunction "C_1_7") (pintype "bidirectional"))
    )
    (net (code "104") (name "unconnected-(IC7-D_2-Pad6)") (class "Default")
      (node (ref "IC7") (pin "6") (pinfunction "D_2_6") (pintype "bidirectional"))
    )
    (net (code "105") (name "unconnected-(IC8-PA1-Pad11)") (class "Default")
      (node (ref "IC8") (pin "11") (pinfunction "PA1_11") (pintype "bidirectional"))
    )
    (net (code "106") (name "unconnected-(IC8-PA2-Pad12)") (class "Default")
      (node (ref "IC8") (pin "12") (pinfunction "PA2_12") (pintype "bidirectional"))
    )
    (net (code "107") (name "unconnected-(IC8-PA3{slash}EXTCLK-Pad13)") (class "Default")
      (node (ref "IC8") (pin "13") (pinfunction "PA3/EXTCLK_13") (pintype "bidirectional"))
    )
    (net (code "108") (name "unconnected-(IC8-PA6-Pad4)") (class "Default")
      (node (ref "IC8") (pin "4") (pinfunction "PA6_4") (pintype "bidirectional"))
    )
    (net (code "109") (name "unconnected-(IC8-PA7-Pad5)") (class "Default")
      (node (ref "IC8") (pin "5") (pinfunction "PA7_5") (pintype "bidirectional"))
    )
    (net (code "110") (name "unconnected-(IC11-CLKOUT-Pad1)") (class "Default")
      (node (ref "IC11") (pin "1") (pinfunction "CLKOUT_1") (pintype "bidirectional"))
    )
    (net (code "111") (name "unconnected-(IC11-EVI-Pad8)") (class "Default")
      (node (ref "IC11") (pin "8") (pinfunction "EVI_8") (pintype "bidirectional"))
    )
    (net (code "112") (name "unconnected-(IC11-~{INT}-Pad2)") (class "Default")
      (node (ref "IC11") (pin "2") (pinfunction "~{INT}_2") (pintype "bidirectional"))
    )
    (net (code "113") (name "unconnected-(U$5-IO-Pad4)") (class "Default")
      (node (ref "U$5") (pin "4") (pinfunction "IO_4") (pintype "passive"))
    )
    (net (code "114") (name "unconnected-(U$5-SHIELD-PadS1)") (class "Default")
      (node (ref "U$5") (pin "S1") (pinfunction "SHIELD_S1") (pintype "passive"))
    )
  )
)
